# cpu.net
KiCad netlist of a schematic drawn in Altium Designer
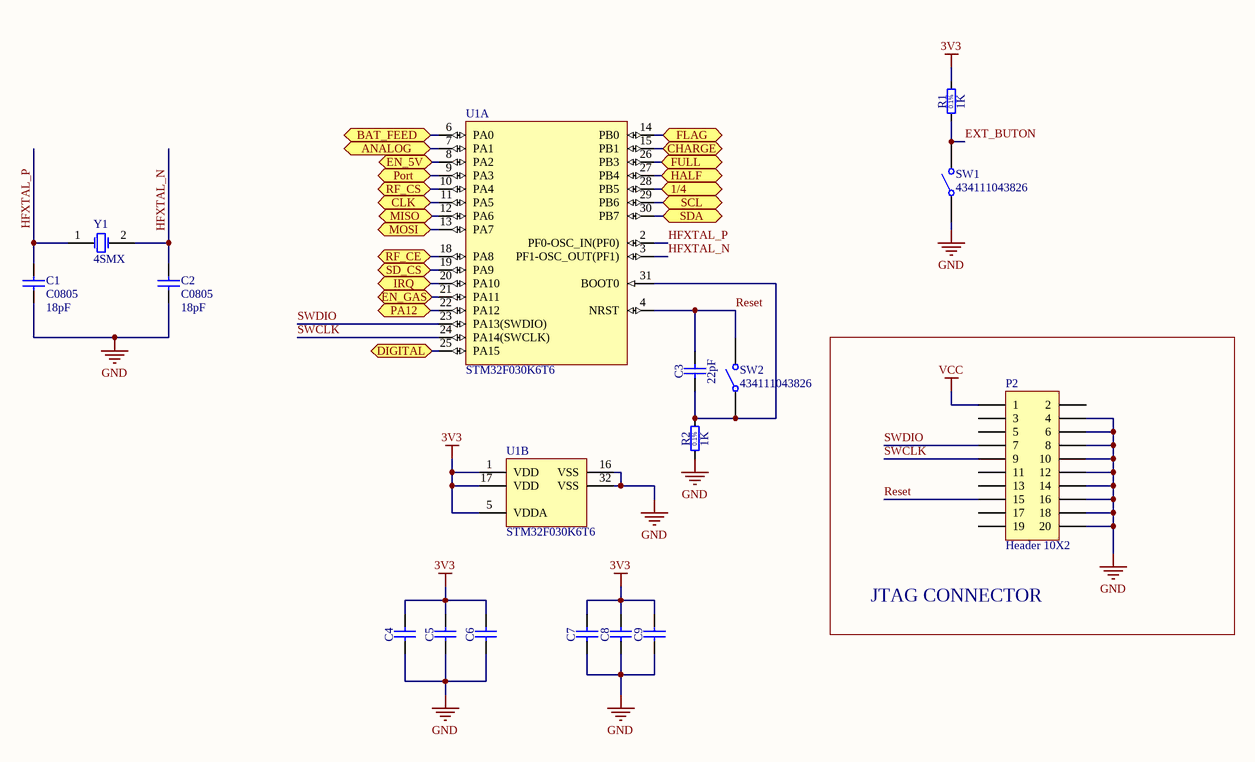
[diagram p0: cpu.SchDoc]

(export (version "E")
  (design (tool "Eeschema 10.0.6"))
  (components
    (comp (ref "C1")
      (value "C0805")
      (footprint "0805")
      (description "Ceramic Chip Capacitor - Standard")
      (fields (field (name "ALTIUM_VALUE") "18pF") (field (name "PUBLISHER") "Altium Limited"))
      (libsource (lib "KEMET Chip Capacitor") (part "C0805"))
    )
    (comp (ref "C2")
      (value "C0805")
      (footprint "0805")
      (description "Ceramic Chip Capacitor - Standard")
      (fields (field (name "ALTIUM_VALUE") "18pF") (field (name "PUBLISHER") "Altium Limited"))
      (libsource (lib "KEMET Chip Capacitor") (part "C0805"))
    )
    (comp (ref "C3")
      (value "22pF")
      (footprint "CAPC2012X135N")
      (description "Non-polarised capacitor")
      (fields
        (field (name "PART NUMBER") "CC0805_10NF_50V_10%_X7R")
        (field (name "VOLTAGE") "50V")
        (field (name "AUTHOR") "CERN DEM JLC")
      )
      (libsource (lib "Capacitors") (part "Capacitor - non polarized"))
    )
    (comp (ref "C4")
      (value "100nF")
      (footprint "CAPC2012X135N")
      (description "Non-polarised capacitor")
      (fields
        (field (name "PART NUMBER") "CC0805_1NF_50V_5%_X7R")
        (field (name "VOLTAGE") "50V")
        (field (name "AUTHOR") "CERN DEM JLC")
      )
      (libsource (lib "Capacitors") (part "Capacitor - non polarized"))
    )
    (comp (ref "C5")
      (value "100nF")
      (footprint "CAPC2012X135N")
      (description "Non-polarised capacitor")
      (fields
        (field (name "PART NUMBER") "CC0805_1NF_50V_5%_X7R")
        (field (name "VOLTAGE") "50V")
        (field (name "AUTHOR") "CERN DEM JLC")
      )
      (libsource (lib "Capacitors") (part "Capacitor - non polarized"))
    )
    (comp (ref "C6")
      (value "100nF")
      (footprint "CAPC2012X135N")
      (description "Non-polarised capacitor")
      (fields
        (field (name "PART NUMBER") "CC0805_1NF_50V_5%_X7R")
        (field (name "VOLTAGE") "50V")
        (field (name "AUTHOR") "CERN DEM JLC")
      )
      (libsource (lib "Capacitors") (part "Capacitor - non polarized"))
    )
    (comp (ref "C7")
      (value "100nF")
      (footprint "CAPC2012X135N")
      (description "Non-polarised capacitor")
      (fields
        (field (name "PART NUMBER") "CC0805_1NF_50V_5%_X7R")
        (field (name "VOLTAGE") "50V")
        (field (name "AUTHOR") "CERN DEM JLC")
      )
      (libsource (lib "Capacitors") (part "Capacitor - non polarized"))
    )
    (comp (ref "C8")
      (value "100nF")
      (footprint "CAPC2012X135N")
      (description "Non-polarised capacitor")
      (fields
        (field (name "PART NUMBER") "CC0805_1NF_50V_5%_X7R")
        (field (name "VOLTAGE") "50V")
        (field (name "AUTHOR") "CERN DEM JLC")
      )
      (libsource (lib "Capacitors") (part "Capacitor - non polarized"))
    )
    (comp (ref "C9")
      (value "100nF")
      (footprint "CAPC2012X135N")
      (description "Non-polarised capacitor")
      (fields
        (field (name "PART NUMBER") "CC0805_1NF_50V_5%_X7R")
        (field (name "VOLTAGE") "50V")
        (field (name "AUTHOR") "CERN DEM JLC")
      )
      (libsource (lib "Capacitors") (part "Capacitor - non polarized"))
    )
    (comp (ref "P2")
      (value "Header 10X2")
      (footprint "HDR2X10")
      (description "Header, 10-Pin, Dual row")
      (fields (field (name "PUBLISHER") "Altium Limited"))
      (libsource (lib "Miscellaneous Connectors") (part "Header 10X2"))
    )
    (comp (ref "R1")
      (value "1K")
      (footprint "RESC2012X60N")
      (description "Resistor - 0.1%")
      (fields
        (field (name "PART NUMBER") "R0805_1K1_0.1%_0.1W_10PPM")
        (field (name "POWER") "0.1W")
        (field (name "AUTHOR") "CERN DEM JLC")
      )
      (libsource (lib "Resistors") (part "Resistor - 0.1%"))
    )
    (comp (ref "R2")
      (value "1K")
      (footprint "RESC2012X60N")
      (description "Resistor - 0.1%")
      (fields
        (field (name "PART NUMBER") "R0805_1K1_0.1%_0.1W_10PPM")
        (field (name "POWER") "0.1W")
        (field (name "AUTHOR") "CERN DEM JLC")
      )
      (libsource (lib "Resistors") (part "Resistor - 0.1%"))
    )
    (comp (ref "SW1")
      (value "434111043826")
      (footprint "434111043826")
      (description "WS-TASV SMD Tact Switch 6.0X3.5 mm")
      (libsource (lib "WS-TASV SMD Tact Switch 6.0X3.5 mm") (part "434111043826"))
    )
    (comp (ref "SW2")
      (value "434111043826")
      (footprint "434111043826")
      (description "WS-TASV SMD Tact Switch 6.0X3.5 mm")
      (libsource (lib "WS-TASV SMD Tact Switch 6.0X3.5 mm") (part "434111043826"))
    )
    (comp (ref "U1")
      (value "STM32F030K6T6")
      (footprint "STM-LQFP32_N")
      (libsource (lib "STMicroelectronics STM32 F0") (part "STM32F030K6T6"))
    )
    (comp (ref "Y1")
      (value "4SMX")
      (footprint "4SMX")
      (description "Surface Mount Quartz Crystal")
      (fields (field (name "PUBLISHER") "Altium Limited"))
      (libsource (lib "C-MAC Crystal Oscillator") (part "4SMX"))
    )
  )
  (nets
    (net (code "1") (name "/1{slash}4") (class "Default")
      (node (ref "U1") (pin "28") (pinfunction "PB5_28") (pintype "bidirectional"))
    )
    (net (code "2") (name "/ANALOG") (class "Default")
      (node (ref "U1") (pin "7") (pinfunction "PA1_7") (pintype "bidirectional"))
    )
    (net (code "3") (name "/BAT_FEED") (class "Default")
      (node (ref "U1") (pin "6") (pinfunction "PA0_6") (pintype "bidirectional"))
    )
    (net (code "4") (name "/CHARGE") (class "Default")
      (node (ref "U1") (pin "15") (pinfunction "PB1_15") (pintype "bidirectional"))
    )
    (net (code "5") (name "/CLK") (class "Default")
      (node (ref "U1") (pin "11") (pinfunction "PA5_11") (pintype "bidirectional"))
    )
    (net (code "6") (name "/DIGITAL") (class "Default")
      (node (ref "U1") (pin "25") (pinfunction "PA15_25") (pintype "bidirectional"))
    )
    (net (code "7") (name "/EN_5V") (class "Default")
      (node (ref "U1") (pin "8") (pinfunction "PA2_8") (pintype "bidirectional"))
    )
    (net (code "8") (name "/EN_GAS") (class "Default")
      (node (ref "U1") (pin "21") (pinfunction "PA11_21") (pintype "bidirectional"))
    )
    (net (code "9") (name "/EXT_BUTON") (class "Default")
      (node (ref "R1") (pin "1") (pinfunction "1_1") (pintype "passive"))
      (node (ref "SW1") (pin "2") (pinfunction "2_2") (pintype "passive"))
    )
    (net (code "10") (name "/FLAG") (class "Default")
      (node (ref "U1") (pin "14") (pinfunction "PB0_14") (pintype "bidirectional"))
    )
    (net (code "11") (name "/FULL") (class "Default")
      (node (ref "U1") (pin "26") (pinfunction "PB3_26") (pintype "bidirectional"))
    )
    (net (code "12") (name "/HALF") (class "Default")
      (node (ref "U1") (pin "27") (pinfunction "PB4_27") (pintype "bidirectional"))
    )
    (net (code "13") (name "/HFXTAL_N") (class "Default")
      (node (ref "C2") (pin "2") (pinfunction "2_2") (pintype "passive"))
      (node (ref "U1") (pin "3") (pinfunction "PF1-OSC_OUT(PF1)_3") (pintype "bidirectional"))
      (node (ref "Y1") (pin "2") (pinfunction "OSC2_2") (pintype "passive"))
    )
    (net (code "14") (name "/HFXTAL_P") (class "Default")
      (node (ref "C1") (pin "2") (pinfunction "2_2") (pintype "passive"))
      (node (ref "U1") (pin "2") (pinfunction "PF0-OSC_IN(PF0)_2") (pintype "bidirectional"))
      (node (ref "Y1") (pin "1") (pinfunction "OSC1_1") (pintype "passive"))
    )
    (net (code "15") (name "/IRQ") (class "Default")
      (node (ref "U1") (pin "20") (pinfunction "PA10_20") (pintype "bidirectional"))
    )
    (net (code "16") (name "/MISO") (class "Default")
      (node (ref "U1") (pin "12") (pinfunction "PA6_12") (pintype "bidirectional"))
    )
    (net (code "17") (name "/MOSI") (class "Default")
      (node (ref "U1") (pin "13") (pinfunction "PA7_13") (pintype "bidirectional"))
    )
    (net (code "18") (name "/PA12") (class "Default")
      (node (ref "U1") (pin "22") (pinfunction "PA12_22") (pintype "bidirectional"))
    )
    (net (code "19") (name "/Port") (class "Default")
      (node (ref "U1") (pin "9") (pinfunction "PA3_9") (pintype "bidirectional"))
    )
    (net (code "20") (name "/RF_CE") (class "Default")
      (node (ref "U1") (pin "18") (pinfunction "PA8_18") (pintype "bidirectional"))
    )
    (net (code "21") (name "/RF_CS") (class "Default")
      (node (ref "U1") (pin "10") (pinfunction "PA4_10") (pintype "bidirectional"))
    )
    (net (code "22") (name "/Reset") (class "Default")
      (node (ref "C3") (pin "2") (pinfunction "2_2") (pintype "passive"))
      (node (ref "P2") (pin "15") (pinfunction "15_15") (pintype "passive"))
      (node (ref "SW2") (pin "2") (pinfunction "2_2") (pintype "passive"))
      (node (ref "U1") (pin "4") (pinfunction "NRST_4") (pintype "bidirectional"))
    )
    (net (code "23") (name "/SCL") (class "Default")
      (node (ref "U1") (pin "29") (pinfunction "PB6_29") (pintype "bidirectional"))
    )
    (net (code "24") (name "/SDA") (class "Default")
      (node (ref "U1") (pin "30") (pinfunction "PB7_30") (pintype "bidirectional"))
    )
    (net (code "25") (name "/SD_CS") (class "Default")
      (node (ref "U1") (pin "19") (pinfunction "PA9_19") (pintype "bidirectional"))
    )
    (net (code "26") (name "/SWCLK") (class "Default")
      (node (ref "P2") (pin "9") (pinfunction "9_9") (pintype "passive"))
      (node (ref "U1") (pin "24") (pinfunction "PA14(SWCLK)_24") (pintype "bidirectional"))
    )
    (net (code "27") (name "/SWDIO") (class "Default")
      (node (ref "P2") (pin "7") (pinfunction "7_7") (pintype "passive"))
      (node (ref "U1") (pin "23") (pinfunction "PA13(SWDIO)_23") (pintype "bidirectional"))
    )
    (net (code "28") (name "3V3") (class "Default")
      (node (ref "C4") (pin "2") (pinfunction "2_2") (pintype "passive"))
      (node (ref "C5") (pin "2") (pinfunction "2_2") (pintype "passive"))
      (node (ref "C6") (pin "2") (pinfunction "2_2") (pintype "passive"))
      (node (ref "C7") (pin "2") (pinfunction "2_2") (pintype "passive"))
      (node (ref "C8") (pin "2") (pinfunction "2_2") (pintype "passive"))
      (node (ref "C9") (pin "2") (pinfunction "2_2") (pintype "passive"))
      (node (ref "R1") (pin "2") (pinfunction "2_2") (pintype "passive"))
      (node (ref "U1") (pin "1") (pinfunction "VDD_1") (pintype "power_in"))
      (node (ref "U1") (pin "17") (pinfunction "VDD_17") (pintype "power_in"))
      (node (ref "U1") (pin "5") (pinfunction "VDDA_5") (pintype "power_in"))
    )
    (net (code "29") (name "GND") (class "Default")
      (node (ref "C1") (pin "1") (pinfunction "1_1") (pintype "passive"))
      (node (ref "C2") (pin "1") (pinfunction "1_1") (pintype "passive"))
      (node (ref "C4") (pin "1") (pinfunction "1_1") (pintype "passive"))
      (node (ref "C5") (pin "1") (pinfunction "1_1") (pintype "passive"))
      (node (ref "C6") (pin "1") (pinfunction "1_1") (pintype "passive"))
      (node (ref "C7") (pin "1") (pinfunction "1_1") (pintype "passive"))
      (node (ref "C8") (pin "1") (pinfunction "1_1") (pintype "passive"))
      (node (ref "C9") (pin "1") (pinfunction "1_1") (pintype "passive"))
      (node (ref "P2") (pin "10") (pinfunction "10_10") (pintype "passive"))
      (node (ref "P2") (pin "12") (pinfunction "12_12") (pintype "passive"))
      (node (ref "P2") (pin "14") (pinfunction "14_14") (pintype "passive"))
      (node (ref "P2") (pin "16") (pinfunction "16_16") (pintype "passive"))
      (node (ref "P2") (pin "18") (pinfunction "18_18") (pintype "passive"))
      (node (ref "P2") (pin "20") (pinfunction "20_20") (pintype "passive"))
      (node (ref "P2") (pin "4") (pinfunction "4_4") (pintype "passive"))
      (node (ref "P2") (pin "6") (pinfunction "6_6") (pintype "passive"))
      (node (ref "P2") (pin "8") (pinfunction "8_8") (pintype "passive"))
      (node (ref "R2") (pin "1") (pinfunction "1_1") (pintype "passive"))
      (node (ref "SW1") (pin "1") (pinfunction "1_1") (pintype "passive"))
      (node (ref "U1") (pin "16") (pinfunction "VSS_16") (pintype "power_in"))
      (node (ref "U1") (pin "32") (pinfunction "VSS_32") (pintype "power_in"))
    )
    (net (code "30") (name "Net-(U1A-BOOT0)") (class "Default")
      (node (ref "C3") (pin "1") (pinfunction "1_1") (pintype "passive"))
      (node (ref "R2") (pin "2") (pinfunction "2_2") (pintype "passive"))
      (node (ref "SW2") (pin "1") (pinfunction "1_1") (pintype "passive"))
      (node (ref "U1") (pin "31") (pinfunction "BOOT0_31") (pintype "input"))
    )
    (net (code "31") (name "VCC") (class "Default")
      (node (ref "P2") (pin "1") (pinfunction "1_1") (pintype "passive"))
    )
    (net (code "32") (name "unconnected-(P2-Pad2)") (class "Default")
      (node (ref "P2") (pin "2") (pinfunction "2_2") (pintype "passive"))
    )
    (net (code "33") (name "unconnected-(P2-Pad3)") (class "Default")
      (node (ref "P2") (pin "3") (pinfunction "3_3") (pintype "passive"))
    )
    (net (code "34") (name "unconnected-(P2-Pad5)") (class "Default")
      (node (ref "P2") (pin "5") (pinfunction "5_5") (pintype "passive"))
    )
    (net (code "35") (name "unconnected-(P2-Pad11)") (class "Default")
      (node (ref "P2") (pin "11") (pinfunction "11_11") (pintype "passive"))
    )
    (net (code "36") (name "unconnected-(P2-Pad13)") (class "Default")
      (node (ref "P2") (pin "13") (pinfunction "13_13") (pintype "passive"))
    )
    (net (code "37") (name "unconnected-(P2-Pad17)") (class "Default")
      (node (ref "P2") (pin "17") (pinfunction "17_17") (pintype "passive"))
    )
    (net (code "38") (name "unconnected-(P2-Pad19)") (class "Default")
      (node (ref "P2") (pin "19") (pinfunction "19_19") (pintype "passive"))
    )
  )
)
